# Adafruit_Feather_RP2040_USB_Host.net
KiCad netlist of a schematic drawn in EAGLE
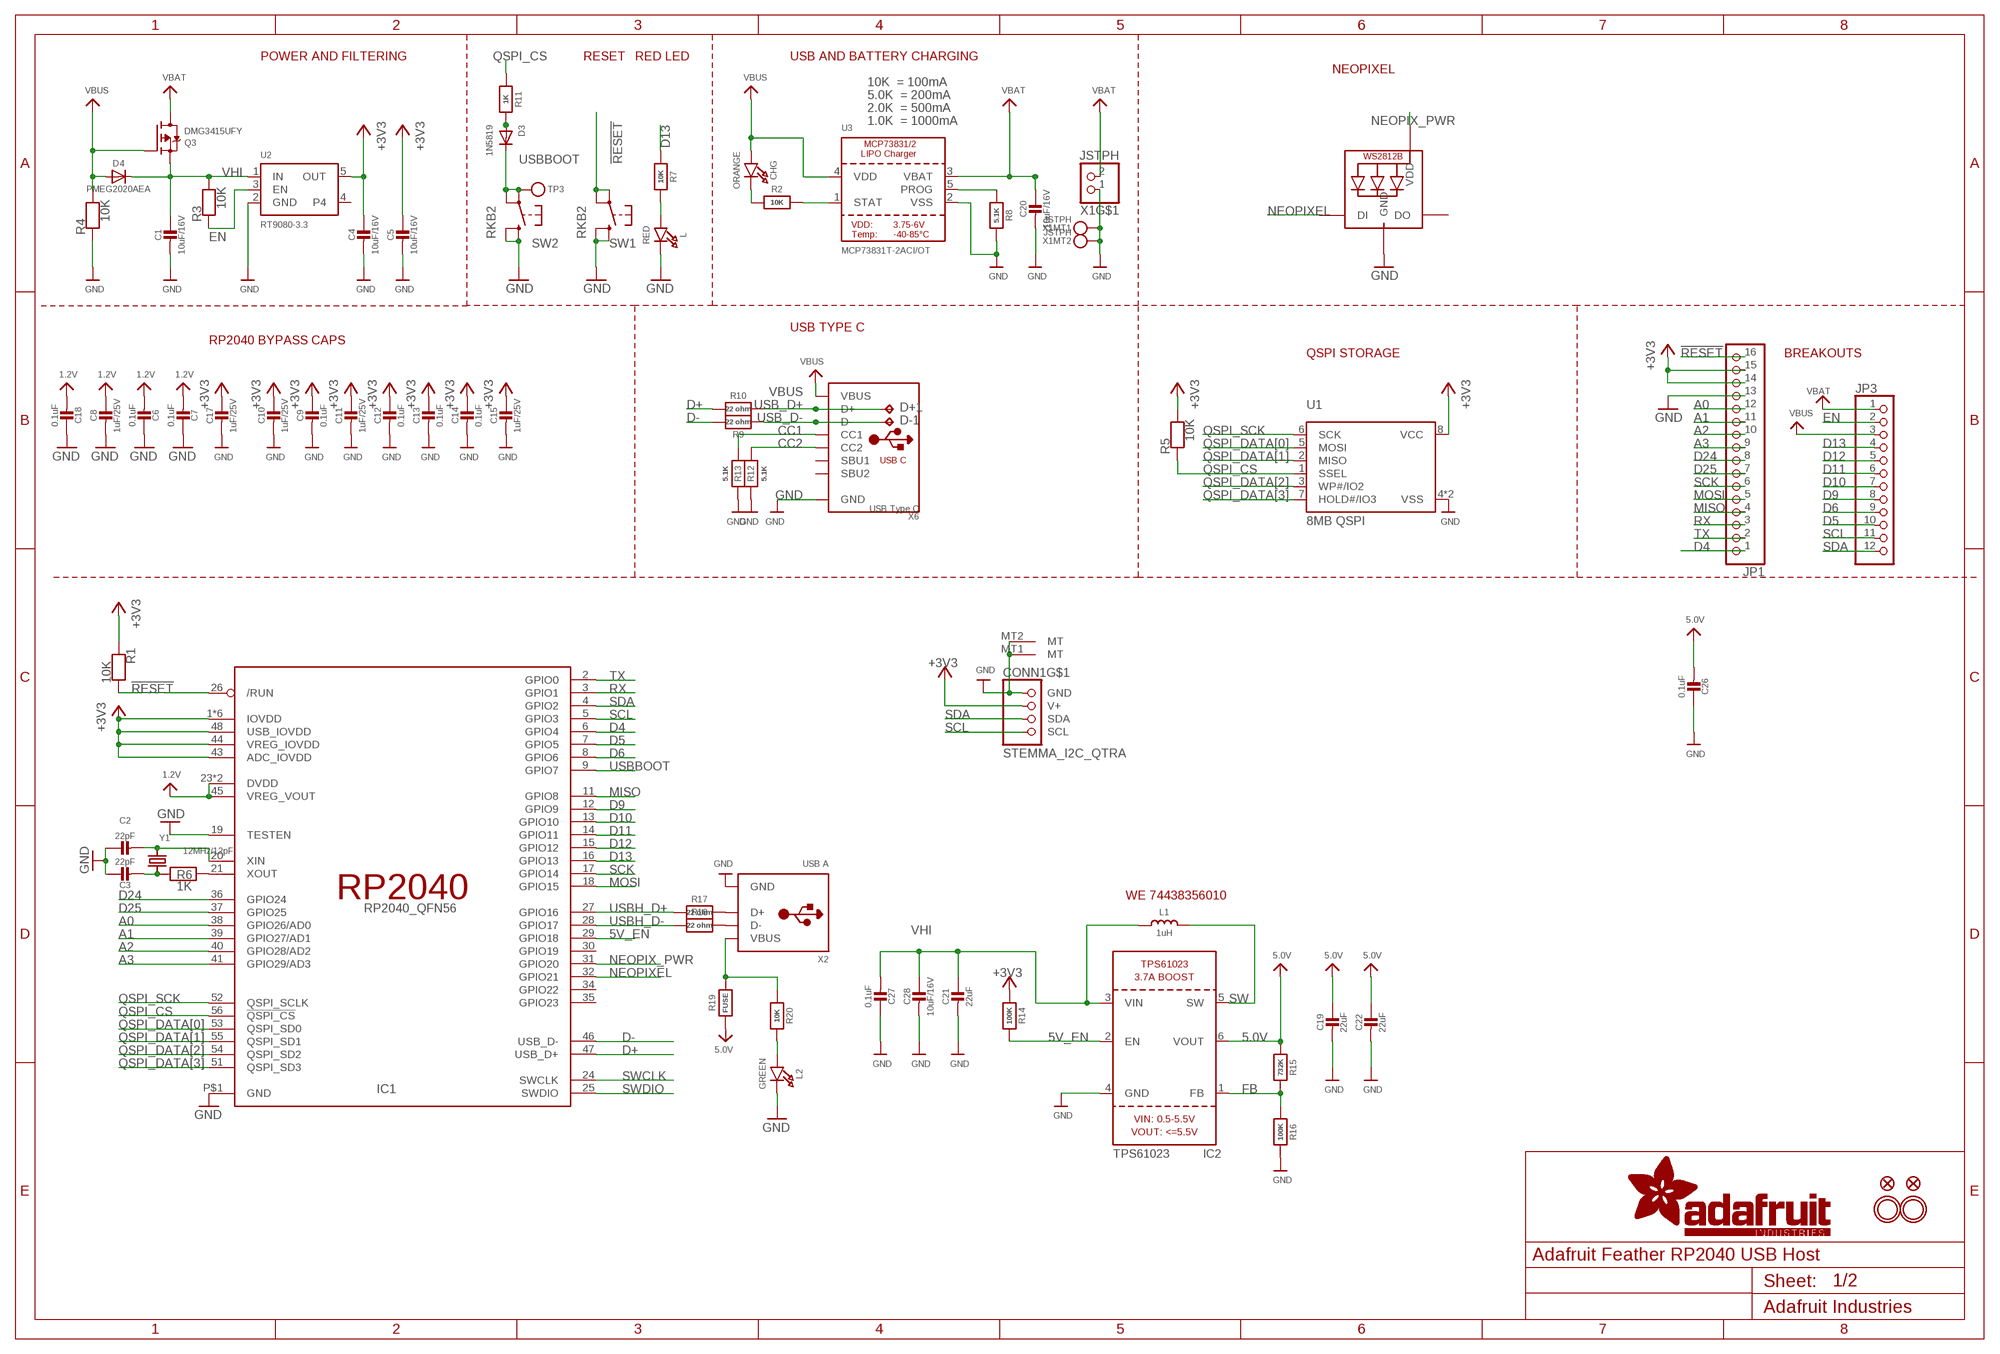
[diagram p0: schematic, sheet 1]

(export (version "E")
  (design (tool "Eeschema 10.0.6"))
  (components
    (comp (ref "C1")
      (value "10uF/16V")
      (footprint "eagle-import:0805-NO")
      (libsource (lib "eagle-import") (part "CAP_CERAMIC0805-NOOUTLINE"))
    )
    (comp (ref "C2")
      (value "22pF")
      (footprint "eagle-import:_0402NO")
      (libsource (lib "eagle-import") (part "CAP_CERAMIC_0402NO"))
    )
    (comp (ref "C3")
      (value "22pF")
      (footprint "eagle-import:_0402NO")
      (libsource (lib "eagle-import") (part "CAP_CERAMIC_0402NO"))
    )
    (comp (ref "C4")
      (value "10uF/16V")
      (footprint "eagle-import:0805-NO")
      (fields (field (name "REV") "A"))
      (libsource (lib "eagle-import") (part "CAP_CERAMIC0805-NOOUTLINE"))
    )
    (comp (ref "C5")
      (value "10uF/16V")
      (footprint "eagle-import:0805-NO")
      (libsource (lib "eagle-import") (part "CAP_CERAMIC0805-NOOUTLINE"))
    )
    (comp (ref "C6")
      (value "0.1uF")
      (footprint "eagle-import:_0402NO")
      (libsource (lib "eagle-import") (part "CAP_CERAMIC_0402NO"))
    )
    (comp (ref "C7")
      (value "0.1uF")
      (footprint "eagle-import:_0402NO")
      (libsource (lib "eagle-import") (part "CAP_CERAMIC_0402NO"))
    )
    (comp (ref "C8")
      (value "1uF/25V")
      (footprint "eagle-import:_0402NO")
      (libsource (lib "eagle-import") (part "CAP_CERAMIC_0402NO"))
    )
    (comp (ref "C9")
      (value "0.1uF")
      (footprint "eagle-import:_0402NO")
      (libsource (lib "eagle-import") (part "CAP_CERAMIC_0402NO"))
    )
    (comp (ref "C10")
      (value "1uF/25V")
      (footprint "eagle-import:_0402NO")
      (libsource (lib "eagle-import") (part "CAP_CERAMIC_0402NO"))
    )
    (comp (ref "C11")
      (value "1uF/25V")
      (footprint "eagle-import:_0402NO")
      (libsource (lib "eagle-import") (part "CAP_CERAMIC_0402NO"))
    )
    (comp (ref "C12")
      (value "0.1uF")
      (footprint "eagle-import:_0402NO")
      (libsource (lib "eagle-import") (part "CAP_CERAMIC_0402NO"))
    )
    (comp (ref "C13")
      (value "0.1uF")
      (footprint "eagle-import:_0402NO")
      (libsource (lib "eagle-import") (part "CAP_CERAMIC_0402NO"))
    )
    (comp (ref "C14")
      (value "0.1uF")
      (footprint "eagle-import:_0402NO")
      (libsource (lib "eagle-import") (part "CAP_CERAMIC_0402NO"))
    )
    (comp (ref "C15")
      (value "1uF/25V")
      (footprint "eagle-import:_0402NO")
      (libsource (lib "eagle-import") (part "CAP_CERAMIC_0402NO"))
    )
    (comp (ref "C17")
      (value "1uF/25V")
      (footprint "eagle-import:_0402NO")
      (libsource (lib "eagle-import") (part "CAP_CERAMIC_0402NO"))
    )
    (comp (ref "C18")
      (value "0.1uF")
      (footprint "eagle-import:_0402NO")
      (libsource (lib "eagle-import") (part "CAP_CERAMIC_0402NO"))
    )
    (comp (ref "C19")
      (value "22uF")
      (footprint "eagle-import:0805-NO")
      (libsource (lib "eagle-import") (part "CAP_CERAMIC0805-NOOUTLINE"))
    )
    (comp (ref "C20")
      (value "10uF/16V")
      (footprint "eagle-import:0805-NO")
      (libsource (lib "eagle-import") (part "CAP_CERAMIC0805-NOOUTLINE"))
    )
    (comp (ref "C21")
      (value "22uF")
      (footprint "eagle-import:0805-NO")
      (libsource (lib "eagle-import") (part "CAP_CERAMIC0805-NOOUTLINE"))
    )
    (comp (ref "C22")
      (value "22uF")
      (footprint "eagle-import:0805-NO")
      (libsource (lib "eagle-import") (part "CAP_CERAMIC0805-NOOUTLINE"))
    )
    (comp (ref "C26")
      (value "0.1uF")
      (footprint "eagle-import:_0402NO")
      (libsource (lib "eagle-import") (part "CAP_CERAMIC_0402NO"))
    )
    (comp (ref "C27")
      (value "0.1uF")
      (footprint "eagle-import:_0402NO")
      (libsource (lib "eagle-import") (part "CAP_CERAMIC_0402NO"))
    )
    (comp (ref "C28")
      (value "10uF/16V")
      (footprint "eagle-import:0805-NO")
      (libsource (lib "eagle-import") (part "CAP_CERAMIC0805-NOOUTLINE"))
    )
    (comp (ref "CHG")
      (value "ORANGE")
      (footprint "eagle-import:CHIPLED_0603_NOOUTLINE")
      (libsource (lib "eagle-import") (part "LED0603_NOOUTLINE"))
    )
    (comp (ref "CONN1")
      (value "STEMMA_I2C_QTRA")
      (footprint "eagle-import:JST_SH4_RA")
      (libsource (lib "eagle-import") (part "STEMMA_I2C_QTRA"))
    )
    (comp (ref "D+1")
      (value "TPB1,27")
      (footprint "eagle-import:B1,27")
      (libsource (lib "eagle-import") (part "TPB1,27"))
    )
    (comp (ref "D-1")
      (value "TPB1,27")
      (footprint "eagle-import:B1,27")
      (libsource (lib "eagle-import") (part "TPB1,27"))
    )
    (comp (ref "D3")
      (value "1N5819")
      (footprint "eagle-import:SOD-323_MINI")
      (libsource (lib "eagle-import") (part "DIODE_SOD323MINI"))
    )
    (comp (ref "D4")
      (value "PMEG2020AEA")
      (footprint "eagle-import:SOD-323F")
      (libsource (lib "eagle-import") (part "DIODESOD-323F"))
    )
    (comp (ref "IC1")
      (value "RP2040_QFN56")
      (footprint "eagle-import:QFN56_7MM_REDUCEDEPAD")
      (libsource (lib "eagle-import") (part "RP2040_QFN56"))
    )
    (comp (ref "IC2")
      (value "TPS61023")
      (footprint "eagle-import:SOT563")
      (libsource (lib "eagle-import") (part "TPS61023"))
    )
    (comp (ref "JP1")
      (value "HEADER-1X16ROUND")
      (footprint "eagle-import:1X16_ROUND")
      (libsource (lib "eagle-import") (part "HEADER-1X16ROUND"))
    )
    (comp (ref "JP3")
      (value "HEADER-1X12")
      (footprint "eagle-import:1X12_ROUND")
      (libsource (lib "eagle-import") (part "HEADER-1X12"))
    )
    (comp (ref "L")
      (value "RED")
      (footprint "eagle-import:CHIPLED_0603_NOOUTLINE")
      (libsource (lib "eagle-import") (part "LED0603_NOOUTLINE"))
    )
    (comp (ref "L1")
      (value "1uH")
      (footprint "eagle-import:INDUCTOR_5045_SMALLTABS")
      (libsource (lib "eagle-import") (part "INDUCTOR_5045_SMALLTABS"))
    )
    (comp (ref "L2")
      (value "GREEN")
      (footprint "eagle-import:CHIPLED_0603_NOOUTLINE")
      (libsource (lib "eagle-import") (part "LED0603_NOOUTLINE"))
    )
    (comp (ref "LED1")
      (value "WS2812B_SK6805_1515")
      (footprint "eagle-import:SK6805_1515")
      (libsource (lib "eagle-import") (part "WS2812B_SK6805_1515"))
    )
    (comp (ref "Q3")
      (value "DMG3415UFY")
      (footprint "eagle-import:DFN2015-3")
      (libsource (lib "eagle-import") (part "MOSFET-P_DFN2015"))
    )
    (comp (ref "R1")
      (value "10K")
      (footprint "eagle-import:_0402NO")
      (libsource (lib "eagle-import") (part "RESISTOR_0402NO"))
    )
    (comp (ref "R2")
      (value "10K")
      (footprint "eagle-import:_0402NO")
      (libsource (lib "eagle-import") (part "RESISTOR_0402NO"))
    )
    (comp (ref "R3")
      (value "10K")
      (footprint "eagle-import:_0402NO")
      (libsource (lib "eagle-import") (part "RESISTOR_0402NO"))
    )
    (comp (ref "R4")
      (value "10K")
      (footprint "eagle-import:_0402NO")
      (libsource (lib "eagle-import") (part "RESISTOR_0402NO"))
    )
    (comp (ref "R5")
      (value "10K")
      (footprint "eagle-import:_0402NO")
      (libsource (lib "eagle-import") (part "RESISTOR_0402NO"))
    )
    (comp (ref "R6")
      (value "1K")
      (footprint "eagle-import:_0402NO")
      (libsource (lib "eagle-import") (part "RESISTOR_0402NO"))
    )
    (comp (ref "R7")
      (value "10K")
      (footprint "eagle-import:_0402NO")
      (libsource (lib "eagle-import") (part "RESISTOR_0402NO"))
    )
    (comp (ref "R8")
      (value "5.1K")
      (footprint "eagle-import:_0402NO")
      (libsource (lib "eagle-import") (part "RESISTOR_0402NO"))
    )
    (comp (ref "R9")
      (value "22 ohm")
      (footprint "eagle-import:_0402NO")
      (libsource (lib "eagle-import") (part "RESISTOR_0402NO"))
    )
    (comp (ref "R10")
      (value "22 ohm")
      (footprint "eagle-import:_0402NO")
      (libsource (lib "eagle-import") (part "RESISTOR_0402NO"))
    )
    (comp (ref "R11")
      (value "1K")
      (footprint "eagle-import:_0402NO")
      (libsource (lib "eagle-import") (part "RESISTOR_0402NO"))
    )
    (comp (ref "R12")
      (value "5.1K")
      (footprint "eagle-import:_0402NO")
      (libsource (lib "eagle-import") (part "RESISTOR_0402NO"))
    )
    (comp (ref "R13")
      (value "5.1K")
      (footprint "eagle-import:_0402NO")
      (libsource (lib "eagle-import") (part "RESISTOR_0402NO"))
    )
    (comp (ref "R14")
      (value "100K")
      (footprint "eagle-import:_0402NO")
      (libsource (lib "eagle-import") (part "RESISTOR_0402NO"))
    )
    (comp (ref "R15")
      (value "732K")
      (footprint "eagle-import:_0402NO")
      (libsource (lib "eagle-import") (part "RESISTOR_0402NO"))
    )
    (comp (ref "R16")
      (value "100K")
      (footprint "eagle-import:_0402NO")
      (libsource (lib "eagle-import") (part "RESISTOR_0402NO"))
    )
    (comp (ref "R17")
      (value "22 ohm")
      (footprint "eagle-import:_0402NO")
      (libsource (lib "eagle-import") (part "RESISTOR_0402NO"))
    )
    (comp (ref "R18")
      (value "22 ohm")
      (footprint "eagle-import:_0402NO")
      (libsource (lib "eagle-import") (part "RESISTOR_0402NO"))
    )
    (comp (ref "R19")
      (value "FUSE")
      (footprint "eagle-import:0805-NO")
      (libsource (lib "eagle-import") (part "RESISTOR0805_NOOUTLINE"))
    )
    (comp (ref "R20")
      (value "10K")
      (footprint "eagle-import:_0402NO")
      (libsource (lib "eagle-import") (part "RESISTOR_0402NO"))
    )
    (comp (ref "SW1")
      (value "RKB2")
      (footprint "eagle-import:BTN_RKB2_4.6X2.8")
      (libsource (lib "eagle-import") (part "SWITCH_TACT_SMT_RKB2"))
    )
    (comp (ref "SW2")
      (value "RKB2")
      (footprint "eagle-import:BTN_RKB2_4.6X2.8")
      (libsource (lib "eagle-import") (part "SWITCH_TACT_SMT_RKB2"))
    )
    (comp (ref "TP3")
      (value "TESTPOINTROUND1.5MMNO")
      (footprint "eagle-import:TESTPOINT_ROUND_1.5MM_NO")
      (libsource (lib "eagle-import") (part "TESTPOINTROUND1.5MMNO"))
    )
    (comp (ref "U$31")
      (value "MOUNTINGHOLE2.5")
      (footprint "eagle-import:MOUNTINGHOLE_2.5_PLATED")
      (libsource (lib "eagle-import") (part "MOUNTINGHOLE2.5"))
    )
    (comp (ref "U$32")
      (value "MOUNTINGHOLE2.5")
      (footprint "eagle-import:MOUNTINGHOLE_2.5_PLATED")
      (libsource (lib "eagle-import") (part "MOUNTINGHOLE2.5"))
    )
    (comp (ref "U$34")
      (value "FIDUCIAL_1MM")
      (footprint "eagle-import:FIDUCIAL_1MM")
      (libsource (lib "eagle-import") (part "FIDUCIAL_1MM"))
    )
    (comp (ref "U$35")
      (value "FIDUCIAL_1MM")
      (footprint "eagle-import:FIDUCIAL_1MM")
      (libsource (lib "eagle-import") (part "FIDUCIAL_1MM"))
    )
    (comp (ref "U1")
      (value "8MB QSPI")
      (footprint "eagle-import:USON8_4X4")
      (libsource (lib "eagle-import") (part "SPIFLASH_8PIN_4X4"))
    )
    (comp (ref "U2")
      (value "RT9080-3.3")
      (footprint "eagle-import:SOT23-5")
      (fields (field (name "JLC_ROTATION") "0"))
      (libsource (lib "eagle-import") (part "VREG_SOT23-5"))
    )
    (comp (ref "U3")
      (value "MCP73831T-2ACI/OT")
      (footprint "eagle-import:SOT23-5")
      (libsource (lib "eagle-import") (part "MCP73831/2"))
    )
    (comp (ref "X1")
      (value "JSTPH")
      (footprint "eagle-import:JSTPH2_BATT")
      (libsource (lib "eagle-import") (part "CON_JST_PH_2PIN_MT_BATT"))
    )
    (comp (ref "X2")
      (value "USB A")
      (footprint "eagle-import:USB_HOST-SMT")
      (libsource (lib "eagle-import") (part "USB_TYPEA_SMT"))
    )
    (comp (ref "X6")
      (value "USB Type C")
      (footprint "eagle-import:USB_C_CUSB31-CFM2AX-01-X")
      (libsource (lib "eagle-import") (part "USB_C"))
    )
    (comp (ref "Y1")
      (value "12MHz/12pF")
      (footprint "eagle-import:CRYSTAL_2.5X2")
      (libsource (lib "eagle-import") (part "CRYSTAL2.5X2.0"))
    )
  )
  (nets
    (net (code "1") (name "+3V3") (class "Default")
      (node (ref "C10") (pin "1") (pinfunction "1_1") (pintype "passive"))
      (node (ref "C11") (pin "1") (pinfunction "1_1") (pintype "passive"))
      (node (ref "C12") (pin "1") (pinfunction "1_1") (pintype "passive"))
      (node (ref "C13") (pin "1") (pinfunction "1_1") (pintype "passive"))
      (node (ref "C14") (pin "1") (pinfunction "1_1") (pintype "passive"))
      (node (ref "C15") (pin "1") (pinfunction "1_1") (pintype "passive"))
      (node (ref "C17") (pin "1") (pinfunction "1_1") (pintype "passive"))
      (node (ref "C4") (pin "1") (pinfunction "1_1") (pintype "passive"))
      (node (ref "C5") (pin "1") (pinfunction "1_1") (pintype "passive"))
      (node (ref "C9") (pin "1") (pinfunction "1_1") (pintype "passive"))
      (node (ref "CONN1") (pin "2") (pinfunction "V+_2") (pintype "passive"))
      (node (ref "IC1") (pin "1") (pinfunction "IOVDD_1") (pintype "power_in"))
      (node (ref "IC1") (pin "10") (pinfunction "IOVDD_10") (pintype "power_in"))
      (node (ref "IC1") (pin "22") (pinfunction "IOVDD_22") (pintype "power_in"))
      (node (ref "IC1") (pin "33") (pinfunction "IOVDD_33") (pintype "power_in"))
      (node (ref "IC1") (pin "42") (pinfunction "IOVDD_42") (pintype "power_in"))
      (node (ref "IC1") (pin "43") (pinfunction "ADC_IOVDD_43") (pintype "power_in"))
      (node (ref "IC1") (pin "44") (pinfunction "VREG_IOVDD_44") (pintype "power_in"))
      (node (ref "IC1") (pin "48") (pinfunction "USB_IOVDD_48") (pintype "power_in"))
      (node (ref "IC1") (pin "49") (pinfunction "IOVDD_49") (pintype "power_in"))
      (node (ref "JP1") (pin "14") (pinfunction "14_14") (pintype "passive"))
      (node (ref "JP1") (pin "15") (pinfunction "15_15") (pintype "passive"))
      (node (ref "R1") (pin "1") (pinfunction "1_1") (pintype "passive"))
      (node (ref "R14") (pin "1") (pinfunction "1_1") (pintype "passive"))
      (node (ref "R5") (pin "2") (pinfunction "2_2") (pintype "passive"))
      (node (ref "U1") (pin "8") (pinfunction "VCC_8") (pintype "bidirectional"))
      (node (ref "U2") (pin "5") (pinfunction "OUT_5") (pintype "power_in"))
    )
    (net (code "2") (name "1.2V") (class "Default")
      (node (ref "C18") (pin "2") (pinfunction "2_2") (pintype "passive"))
      (node (ref "C6") (pin "2") (pinfunction "2_2") (pintype "passive"))
      (node (ref "C7") (pin "2") (pinfunction "2_2") (pintype "passive"))
      (node (ref "C8") (pin "1") (pinfunction "1_1") (pintype "passive"))
      (node (ref "IC1") (pin "23") (pinfunction "DVDD_23") (pintype "power_in"))
      (node (ref "IC1") (pin "45") (pinfunction "VREG_VOUT_45") (pintype "power_in"))
      (node (ref "IC1") (pin "50") (pinfunction "DVDD_50") (pintype "power_in"))
    )
    (net (code "3") (name "5.0V") (class "Default")
      (node (ref "C19") (pin "1") (pinfunction "1_1") (pintype "passive"))
      (node (ref "C22") (pin "1") (pinfunction "1_1") (pintype "passive"))
      (node (ref "C26") (pin "2") (pinfunction "2_2") (pintype "passive"))
      (node (ref "IC2") (pin "6") (pinfunction "VOUT_6") (pintype "power_in"))
      (node (ref "R15") (pin "1") (pinfunction "1_1") (pintype "passive"))
      (node (ref "R19") (pin "2") (pinfunction "2_2") (pintype "passive"))
    )
    (net (code "4") (name "5V_EN") (class "Default")
      (node (ref "IC1") (pin "29") (pinfunction "GPIO18_29") (pintype "bidirectional"))
      (node (ref "IC2") (pin "2") (pinfunction "EN_2") (pintype "input"))
      (node (ref "R14") (pin "2") (pinfunction "2_2") (pintype "passive"))
    )
    (net (code "5") (name "A0") (class "Default")
      (node (ref "IC1") (pin "38") (pinfunction "GPIO26/AD0_38") (pintype "bidirectional"))
      (node (ref "JP1") (pin "12") (pinfunction "12_12") (pintype "passive"))
    )
    (net (code "6") (name "A1") (class "Default")
      (node (ref "IC1") (pin "39") (pinfunction "GPIO27/AD1_39") (pintype "bidirectional"))
      (node (ref "JP1") (pin "11") (pinfunction "11_11") (pintype "passive"))
    )
    (net (code "7") (name "A2") (class "Default")
      (node (ref "IC1") (pin "40") (pinfunction "GPIO28/AD2_40") (pintype "bidirectional"))
      (node (ref "JP1") (pin "10") (pinfunction "10_10") (pintype "passive"))
    )
    (net (code "8") (name "A3") (class "Default")
      (node (ref "IC1") (pin "41") (pinfunction "GPIO29/AD3_41") (pintype "bidirectional"))
      (node (ref "JP1") (pin "9") (pinfunction "9_9") (pintype "passive"))
    )
    (net (code "9") (name "CC1") (class "Default")
      (node (ref "R13") (pin "2") (pinfunction "2_2") (pintype "passive"))
      (node (ref "X6") (pin "A5") (pinfunction "CC1_A5") (pintype "bidirectional"))
    )
    (net (code "10") (name "CC2") (class "Default")
      (node (ref "R12") (pin "2") (pinfunction "2_2") (pintype "passive"))
      (node (ref "X6") (pin "B5") (pinfunction "CC2_B5") (pintype "bidirectional"))
    )
    (net (code "11") (name "D+") (class "Default")
      (node (ref "IC1") (pin "47") (pinfunction "USB_D+_47") (pintype "bidirectional"))
      (node (ref "R10") (pin "2") (pinfunction "2_2") (pintype "passive"))
    )
    (net (code "12") (name "D-") (class "Default")
      (node (ref "IC1") (pin "46") (pinfunction "USB_D-_46") (pintype "bidirectional"))
      (node (ref "R9") (pin "2") (pinfunction "2_2") (pintype "passive"))
    )
    (net (code "13") (name "D4") (class "Default")
      (node (ref "IC1") (pin "6") (pinfunction "GPIO4_6") (pintype "bidirectional"))
      (node (ref "JP1") (pin "1") (pinfunction "1_1") (pintype "passive"))
    )
    (net (code "14") (name "D5") (class "Default")
      (node (ref "IC1") (pin "7") (pinfunction "GPIO5_7") (pintype "bidirectional"))
      (node (ref "JP3") (pin "10") (pinfunction "10_10") (pintype "passive"))
    )
    (net (code "15") (name "D6") (class "Default")
      (node (ref "IC1") (pin "8") (pinfunction "GPIO6_8") (pintype "bidirectional"))
      (node (ref "JP3") (pin "9") (pinfunction "9_9") (pintype "passive"))
    )
    (net (code "16") (name "D9") (class "Default")
      (node (ref "IC1") (pin "12") (pinfunction "GPIO9_12") (pintype "bidirectional"))
      (node (ref "JP3") (pin "8") (pinfunction "8_8") (pintype "passive"))
    )
    (net (code "17") (name "D10") (class "Default")
      (node (ref "IC1") (pin "13") (pinfunction "GPIO10_13") (pintype "bidirectional"))
      (node (ref "JP3") (pin "7") (pinfunction "7_7") (pintype "passive"))
    )
    (net (code "18") (name "D11") (class "Default")
      (node (ref "IC1") (pin "14") (pinfunction "GPIO11_14") (pintype "bidirectional"))
      (node (ref "JP3") (pin "6") (pinfunction "6_6") (pintype "passive"))
    )
    (net (code "19") (name "D12") (class "Default")
      (node (ref "IC1") (pin "15") (pinfunction "GPIO12_15") (pintype "bidirectional"))
      (node (ref "JP3") (pin "5") (pinfunction "5_5") (pintype "passive"))
    )
    (net (code "20") (name "D13") (class "Default")
      (node (ref "IC1") (pin "16") (pinfunction "GPIO13_16") (pintype "bidirectional"))
      (node (ref "JP3") (pin "4") (pinfunction "4_4") (pintype "passive"))
      (node (ref "R7") (pin "1") (pinfunction "1_1") (pintype "passive"))
    )
    (net (code "21") (name "D24") (class "Default")
      (node (ref "IC1") (pin "36") (pinfunction "GPIO24_36") (pintype "bidirectional"))
      (node (ref "JP1") (pin "8") (pinfunction "8_8") (pintype "passive"))
    )
    (net (code "22") (name "D25") (class "Default")
      (node (ref "IC1") (pin "37") (pinfunction "GPIO25_37") (pintype "bidirectional"))
      (node (ref "JP1") (pin "7") (pinfunction "7_7") (pintype "passive"))
    )
    (net (code "23") (name "EN") (class "Default")
      (node (ref "JP3") (pin "2") (pinfunction "2_2") (pintype "passive"))
      (node (ref "R3") (pin "1") (pinfunction "1_1") (pintype "passive"))
      (node (ref "U2") (pin "3") (pinfunction "EN_3") (pintype "input"))
    )
    (net (code "24") (name "FB") (class "Default")
      (node (ref "IC2") (pin "1") (pinfunction "FB_1") (pintype "input"))
      (node (ref "R15") (pin "2") (pinfunction "2_2") (pintype "passive"))
      (node (ref "R16") (pin "1") (pinfunction "1_1") (pintype "passive"))
    )
    (net (code "25") (name "GND") (class "Default")
      (node (ref "C1") (pin "2") (pinfunction "2_2") (pintype "passive"))
      (node (ref "C10") (pin "2") (pinfunction "2_2") (pintype "passive"))
      (node (ref "C11") (pin "2") (pinfunction "2_2") (pintype "passive"))
      (node (ref "C12") (pin "2") (pinfunction "2_2") (pintype "passive"))
      (node (ref "C13") (pin "2") (pinfunction "2_2") (pintype "passive"))
      (node (ref "C14") (pin "2") (pinfunction "2_2") (pintype "passive"))
      (node (ref "C15") (pin "2") (pinfunction "2_2") (pintype "passive"))
      (node (ref "C17") (pin "2") (pinfunction "2_2") (pintype "passive"))
      (node (ref "C18") (pin "1") (pinfunction "1_1") (pintype "passive"))
      (node (ref "C19") (pin "2") (pinfunction "2_2") (pintype "passive"))
      (node (ref "C2") (pin "1") (pinfunction "1_1") (pintype "passive"))
      (node (ref "C20") (pin "2") (pinfunction "2_2") (pintype "passive"))
      (node (ref "C21") (pin "2") (pinfunction "2_2") (pintype "passive"))
      (node (ref "C22") (pin "2") (pinfunction "2_2") (pintype "passive"))
      (node (ref "C26") (pin "1") (pinfunction "1_1") (pintype "passive"))
      (node (ref "C27") (pin "1") (pinfunction "1_1") (pintype "passive"))
      (node (ref "C28") (pin "2") (pinfunction "2_2") (pintype "passive"))
      (node (ref "C3") (pin "1") (pinfunction "1_1") (pintype "passive"))
      (node (ref "C4") (pin "2") (pinfunction "2_2") (pintype "passive"))
      (node (ref "C5") (pin "2") (pinfunction "2_2") (pintype "passive"))
      (node (ref "C6") (pin "1") (pinfunction "1_1") (pintype "passive"))
      (node (ref "C7") (pin "1") (pinfunction "1_1") (pintype "passive"))
      (node (ref "C8") (pin "2") (pinfunction "2_2") (pintype "passive"))
      (node (ref "C9") (pin "2") (pinfunction "2_2") (pintype "passive"))
      (node (ref "CONN1") (pin "1") (pinfunction "GND_1") (pintype "passive"))
      (node (ref "CONN1") (pin "MT1") (pinfunction "MT_MT1") (pintype "bidirectional"))
      (node (ref "CONN1") (pin "MT2") (pinfunction "MT_MT2") (pintype "bidirectional"))
      (node (ref "IC1") (pin "19") (pinfunction "TESTEN_19") (pintype "input"))
      (node (ref "IC1") (pin "P$1") (pinfunction "GND_P$1") (pintype "power_in"))
      (node (ref "IC2") (pin "4") (pinfunction "GND_4") (pintype "power_in"))
      (node (ref "JP1") (pin "13") (pinfunction "13_13") (pintype "passive"))
      (node (ref "L") (pin "C") (pinfunction "C_C") (pintype "passive"))
      (node (ref "L2") (pin "C") (pinfunction "C_C") (pintype "passive"))
      (node (ref "LED1") (pin "4") (pinfunction "GND_4") (pintype "power_in"))
      (node (ref "R12") (pin "1") (pinfunction "1_1") (pintype "passive"))
      (node (ref "R13") (pin "1") (pinfunction "1_1") (pintype "passive"))
      (node (ref "R16") (pin "2") (pinfunction "2_2") (pintype "passive"))
      (node (ref "R4") (pin "1") (pinfunction "1_1") (pintype "passive"))
      (node (ref "R8") (pin "2") (pinfunction "2_2") (pintype "passive"))
      (node (ref "SW1") (pin "B") (pinfunction "S_B") (pintype "passive"))
      (node (ref "SW1") (pin "B'") (pinfunction "S1_B'") (pintype "passive"))
      (node (ref "SW2") (pin "B") (pinfunction "S_B") (pintype "passive"))
      (node (ref "SW2") (pin "B'") (pinfunction "S1_B'") (pintype "passive"))
      (node (ref "U1") (pin "4") (pinfunction "VSS_4") (pintype "bidirectional"))
      (node (ref "U1") (pin "PAD") (pinfunction "VSS_PAD") (pintype "bidirectional"))
      (node (ref "U2") (pin "2") (pinfunction "GND_2") (pintype "power_in"))
      (node (ref "U3") (pin "2") (pinfunction "VSS_2") (pintype "power_in"))
      (node (ref "X1") (pin "1") (pinfunction "1_1") (pintype "passive"))
      (node (ref "X1") (pin "NC1") (pinfunction "P$1_NC1") (pintype "bidirectional"))
      (node (ref "X1") (pin "NC2") (pinfunction "P$1_NC2") (pintype "bidirectional"))
      (node (ref "X2") (pin "GND") (pinfunction "GND_GND") (pintype "power_in"))
      (node (ref "X6") (pin "A1B12") (pinfunction "GND_A1B12") (pintype "power_in"))
      (node (ref "X6") (pin "B1A12") (pinfunction "GND_B1A12") (pintype "power_in"))
    )
    (net (code "26") (name "MISO") (class "Default")
      (node (ref "IC1") (pin "11") (pinfunction "GPIO8_11") (pintype "bidirectional"))
      (node (ref "JP1") (pin "4") (pinfunction "4_4") (pintype "passive"))
    )
    (net (code "27") (name "MOSI") (class "Default")
      (node (ref "IC1") (pin "18") (pinfunction "GPIO15_18") (pintype "bidirectional"))
      (node (ref "JP1") (pin "5") (pinfunction "5_5") (pintype "passive"))
    )
    (net (code "28") (name "NEOPIXEL") (class "Default")
      (node (ref "IC1") (pin "32") (pinfunction "GPIO21_32") (pintype "bidirectional"))
      (node (ref "LED1") (pin "1") (pinfunction "DI_1") (pintype "input"))
    )
    (net (code "29") (name "NEOPIX_PWR") (class "Default")
      (node (ref "IC1") (pin "31") (pinfunction "GPIO20_31") (pintype "bidirectional"))
      (node (ref "LED1") (pin "2") (pinfunction "VDD_2") (pintype "power_in"))
    )
    (net (code "30") (name "Net-(C3-Pad2)") (class "Default")
      (node (ref "C3") (pin "2") (pinfunction "2_2") (pintype "passive"))
      (node (ref "R6") (pin "1") (pinfunction "1_1") (pintype "passive"))
      (node (ref "Y1") (pin "1") (pinfunction "1_1") (pintype "passive"))
    )
    (net (code "31") (name "Net-(CHG-PadC)") (class "Default")
      (node (ref "CHG") (pin "C") (pinfunction "C_C") (pintype "passive"))
      (node (ref "R2") (pin "1") (pinfunction "1_1") (pintype "passive"))
    )
    (net (code "32") (name "Net-(D3-PadA)") (class "Default")
      (node (ref "D3") (pin "A") (pinfunction "A_A") (pintype "passive"))
      (node (ref "R11") (pin "2") (pinfunction "2_2") (pintype "passive"))
    )
    (net (code "33") (name "Net-(IC1-XIN)") (class "Default")
      (node (ref "C2") (pin "2") (pinfunction "2_2") (pintype "passive"))
      (node (ref "IC1") (pin "20") (pinfunction "XIN_20") (pintype "input"))
      (node (ref "Y1") (pin "3") (pinfunction "2_3") (pintype "passive"))
    )
    (net (code "34") (name "Net-(IC1-XOUT)") (class "Default")
      (node (ref "IC1") (pin "21") (pinfunction "XOUT_21") (pintype "output"))
      (node (ref "R6") (pin "2") (pinfunction "2_2") (pintype "passive"))
    )
    (net (code "35") (name "Net-(L-PadA)") (class "Default")
      (node (ref "L") (pin "A") (pinfunction "A_A") (pintype "passive"))
      (node (ref "R7") (pin "2") (pinfunction "2_2") (pintype "passive"))
    )
    (net (code "36") (name "Net-(L2-PadA)") (class "Default")
      (node (ref "L2") (pin "A") (pinfunction "A_A") (pintype "passive"))
      (node (ref "R20") (pin "2") (pinfunction "2_2") (pintype "passive"))
    )
    (net (code "37") (name "Net-(R17-Pad1)") (class "Default")
      (node (ref "R17") (pin "1") (pinfunction "1_1") (pintype "passive"))
      (node (ref "X2") (pin "D+") (pinfunction "D+_D+") (pintype "bidirectional"))
    )
    (net (code "38") (name "Net-(R18-Pad1)") (class "Default")
      (node (ref "R18") (pin "1") (pinfunction "1_1") (pintype "passive"))
      (node (ref "X2") (pin "D-") (pinfunction "D-_D-") (pintype "bidirectional"))
    )
    (net (code "39") (name "Net-(R19-Pad1)") (class "Default")
      (node (ref "R19") (pin "1") (pinfunction "1_1") (pintype "passive"))
      (node (ref "R20") (pin "1") (pinfunction "1_1") (pintype "passive"))
      (node (ref "X2") (pin "VBUS") (pinfunction "VBUS_VBUS") (pintype "power_in"))
    )
    (net (code "40") (name "Net-(U3-PROG)") (class "Default")
      (node (ref "R8") (pin "1") (pinfunction "1_1") (pintype "passive"))
      (node (ref "U3") (pin "5") (pinfunction "PROG_5") (pintype "input"))
    )
    (net (code "41") (name "Net-(U3-STAT)") (class "Default")
      (node (ref "R2") (pin "2") (pinfunction "2_2") (pintype "passive"))
      (node (ref "U3") (pin "1") (pinfunction "STAT_1") (pintype "output"))
    )
    (net (code "42") (name "QSPI_CS") (class "Default")
      (node (ref "IC1") (pin "56") (pinfunction "~{QSPI_CS}_56") (pintype "bidirectional"))
      (node (ref "R11") (pin "1") (pinfunction "1_1") (pintype "passive"))
      (node (ref "R5") (pin "1") (pinfunction "1_1") (pintype "passive"))
      (node (ref "U1") (pin "1") (pinfunction "SSEL_1") (pintype "bidirectional"))
    )
    (net (code "43") (name "QSPI_DATA[0]") (class "Default")
      (node (ref "IC1") (pin "53") (pinfunction "QSPI_SD0_53") (pintype "bidirectional"))
      (node (ref "U1") (pin "5") (pinfunction "MOSI_5") (pintype "bidirectional"))
    )
    (net (code "44") (name "QSPI_DATA[1]") (class "Default")
      (node (ref "IC1") (pin "55") (pinfunction "QSPI_SD1_55") (pintype "bidirectional"))
      (node (ref "U1") (pin "2") (pinfunction "MISO_2") (pintype "bidirectional"))
    )
    (net (code "45") (name "QSPI_DATA[2]") (class "Default")
      (node (ref "IC1") (pin "54") (pinfunction "QSPI_SD2_54") (pintype "bidirectional"))
      (node (ref "U1") (pin "3") (pinfunction "WP#/IO2_3") (pintype "bidirectional"))
    )
    (net (code "46") (name "QSPI_DATA[3]") (class "Default")
      (node (ref "IC1") (pin "51") (pinfunction "QSPI_SD3_51") (pintype "bidirectional"))
      (node (ref "U1") (pin "7") (pinfunction "HOLD#/IO3_7") (pintype "bidirectional"))
    )
    (net (code "47") (name "QSPI_SCK") (class "Default")
      (node (ref "IC1") (pin "52") (pinfunction "QSPI_SCLK_52") (pintype "bidirectional"))
      (node (ref "U1") (pin "6") (pinfunction "SCK_6") (pintype "bidirectional"))
    )
    (net (code "48") (name "RX") (class "Default")
      (node (ref "IC1") (pin "3") (pinfunction "GPIO1_3") (pintype "bidirectional"))
      (node (ref "JP1") (pin "3") (pinfunction "3_3") (pintype "passive"))
    )
    (net (code "49") (name "SCK") (class "Default")
      (node (ref "IC1") (pin "17") (pinfunction "GPIO14_17") (pintype "bidirectional"))
      (node (ref "JP1") (pin "6") (pinfunction "6_6") (pintype "passive"))
    )
    (net (code "50") (name "SCL") (class "Default")
      (node (ref "CONN1") (pin "4") (pinfunction "SCL_4") (pintype "passive"))
      (node (ref "IC1") (pin "5") (pinfunction "GPIO3_5") (pintype "bidirectional"))
      (node (ref "JP3") (pin "11") (pinfunction "11_11") (pintype "passive"))
    )
    (net (code "51") (name "SDA") (class "Default")
      (node (ref "CONN1") (pin "3") (pinfunction "SDA_3") (pintype "passive"))
      (node (ref "IC1") (pin "4") (pinfunction "GPIO2_4") (pintype "bidirectional"))
      (node (ref "JP3") (pin "12") (pinfunction "12_12") (pintype "passive"))
    )
    (net (code "52") (name "SW") (class "Default")
      (node (ref "IC2") (pin "5") (pinfunction "SW_5") (pintype "input"))
      (node (ref "L1") (pin "2") (pinfunction "2_2") (pintype "passive"))
    )
    (net (code "53") (name "SWCLK") (class "Default")
      (node (ref "IC1") (pin "24") (pinfunction "SWCLK_24") (pintype "bidirectional"))
    )
    (net (code "54") (name "SWDIO") (class "Default")
      (node (ref "IC1") (pin "25") (pinfunction "SWDIO_25") (pintype "bidirectional"))
    )
    (net (code "55") (name "TX") (class "Default")
      (node (ref "IC1") (pin "2") (pinfunction "GPIO0_2") (pintype "bidirectional"))
      (node (ref "JP1") (pin "2") (pinfunction "2_2") (pintype "passive"))
    )
    (net (code "56") (name "USBBOOT") (class "Default")
      (node (ref "D3") (pin "C") (pinfunction "C_C") (pintype "passive"))
      (node (ref "IC1") (pin "9") (pinfunction "GPIO7_9") (pintype "bidirectional"))
      (node (ref "SW2") (pin "A") (pinfunction "P_A") (pintype "passive"))
      (node (ref "SW2") (pin "A'") (pinfunction "P1_A'") (pintype "passive"))
      (node (ref "TP3") (pin "P$1") (pinfunction "P$1_P$1") (pintype "bidirectional"))
    )
    (net (code "57") (name "USBH_D+") (class "Default")
      (node (ref "IC1") (pin "27") (pinfunction "GPIO16_27") (pintype "bidirectional"))
      (node (ref "R17") (pin "2") (pinfunction "2_2") (pintype "passive"))
    )
    (net (code "58") (name "USBH_D-") (class "Default")
      (node (ref "IC1") (pin "28") (pinfunction "GPIO17_28") (pintype "bidirectional"))
      (node (ref "R18") (pin "2") (pinfunction "2_2") (pintype "passive"))
    )
    (net (code "59") (name "USB_D+") (class "Default")
      (node (ref "D+1") (pin "TP") (pinfunction "TP_TP") (pintype "input"))
      (node (ref "R10") (pin "1") (pinfunction "1_1") (pintype "passive"))
      (node (ref "X6") (pin "A6") (pinfunction "D+_A6") (pintype "bidirectional"))
      (node (ref "X6") (pin "B6") (pinfunction "D+_B6") (pintype "bidirectional"))
    )
    (net (code "60") (name "USB_D-") (class "Default")
      (node (ref "D-1") (pin "TP") (pinfunction "TP_TP") (pintype "input"))
      (node (ref "R9") (pin "1") (pinfunction "1_1") (pintype "passive"))
      (node (ref "X6") (pin "A7") (pinfunction "D-_A7") (pintype "bidirectional"))
      (node (ref "X6") (pin "B7") (pinfunction "D-_B7") (pintype "bidirectional"))
    )
    (net (code "61") (name "VBAT") (class "Default")
      (node (ref "C20") (pin "1") (pinfunction "1_1") (pintype "passive"))
      (node (ref "JP3") (pin "1") (pinfunction "1_1") (pintype "passive"))
      (node (ref "Q3") (pin "3") (pinfunction "D_3") (pintype "passive"))
      (node (ref "U3") (pin "3") (pinfunction "VBAT_3") (pintype "power_in"))
      (node (ref "X1") (pin "2") (pinfunction "2_2") (pintype "passive"))
    )
    (net (code "62") (name "VBUS") (class "Default")
      (node (ref "CHG") (pin "A") (pinfunction "A_A") (pintype "passive"))
      (node (ref "D4") (pin "A") (pinfunction "A_A") (pintype "passive"))
      (node (ref "JP3") (pin "3") (pinfunction "3_3") (pintype "passive"))
      (node (ref "Q3") (pin "1") (pinfunction "G_1") (pintype "passive"))
      (node (ref "R4") (pin "2") (pinfunction "2_2") (pintype "passive"))
      (node (ref "U3") (pin "4") (pinfunction "VDD_4") (pintype "power_in"))
      (node (ref "X6") (pin "A4B9") (pinfunction "VBUS_A4B9") (pintype "power_in"))
      (node (ref "X6") (pin "B4A9") (pinfunction "VBUS_B4A9") (pintype "power_in"))
    )
    (net (code "63") (name "VHI") (class "Default")
      (node (ref "C1") (pin "1") (pinfunction "1_1") (pintype "passive"))
      (node (ref "C21") (pin "1") (pinfunction "1_1") (pintype "passive"))
      (node (ref "C27") (pin "2") (pinfunction "2_2") (pintype "passive"))
      (node (ref "C28") (pin "1") (pinfunction "1_1") (pintype "passive"))
      (node (ref "D4") (pin "C") (pinfunction "C_C") (pintype "passive"))
      (node (ref "IC2") (pin "3") (pinfunction "VIN_3") (pintype "power_in"))
      (node (ref "L1") (pin "1") (pinfunction "1_1") (pintype "passive"))
      (node (ref "Q3") (pin "2") (pinfunction "S_2") (pintype "passive"))
      (node (ref "R3") (pin "2") (pinfunction "2_2") (pintype "passive"))
      (node (ref "U2") (pin "1") (pinfunction "IN_1") (pintype "power_in"))
    )
    (net (code "64") (name "unconnected-(IC1-GPIO19-Pad30)") (class "Default")
      (node (ref "IC1") (pin "30") (pinfunction "GPIO19_30") (pintype "bidirectional"))
    )
    (net (code "65") (name "unconnected-(IC1-GPIO22-Pad34)") (class "Default")
      (node (ref "IC1") (pin "34") (pinfunction "GPIO22_34") (pintype "bidirectional"))
    )
    (net (code "66") (name "unconnected-(IC1-GPIO23-Pad35)") (class "Default")
      (node (ref "IC1") (pin "35") (pinfunction "GPIO23_35") (pintype "bidirectional"))
    )
    (net (code "67") (name "unconnected-(LED1-DO-Pad3)") (class "Default")
      (node (ref "LED1") (pin "3") (pinfunction "DO_3") (pintype "output"))
    )
    (net (code "68") (name "unconnected-(U2-P4-Pad4)") (class "Default")
      (node (ref "U2") (pin "4") (pinfunction "P4_4") (pintype "bidirectional"))
    )
    (net (code "69") (name "unconnected-(X6-SBU1-PadA8)") (class "Default")
      (node (ref "X6") (pin "A8") (pinfunction "SBU1_A8") (pintype "bidirectional"))
    )
    (net (code "70") (name "unconnected-(X6-SBU2-PadB8)") (class "Default")
      (node (ref "X6") (pin "B8") (pinfunction "SBU2_B8") (pintype "bidirectional"))
    )
    (net (code "71") (name "~{RESET}") (class "Default")
      (node (ref "IC1") (pin "26") (pinfunction "/RUN_26") (pintype "bidirectional"))
      (node (ref "JP1") (pin "16") (pinfunction "16_16") (pintype "passive"))
      (node (ref "R1") (pin "2") (pinfunction "2_2") (pintype "passive"))
      (node (ref "SW1") (pin "A") (pinfunction "P_A") (pintype "passive"))
      (node (ref "SW1") (pin "A'") (pinfunction "P1_A'") (pintype "passive"))
    )
  )
)
